# CW308T_AURIX.net
KiCad netlist of a schematic drawn in Altium Designer
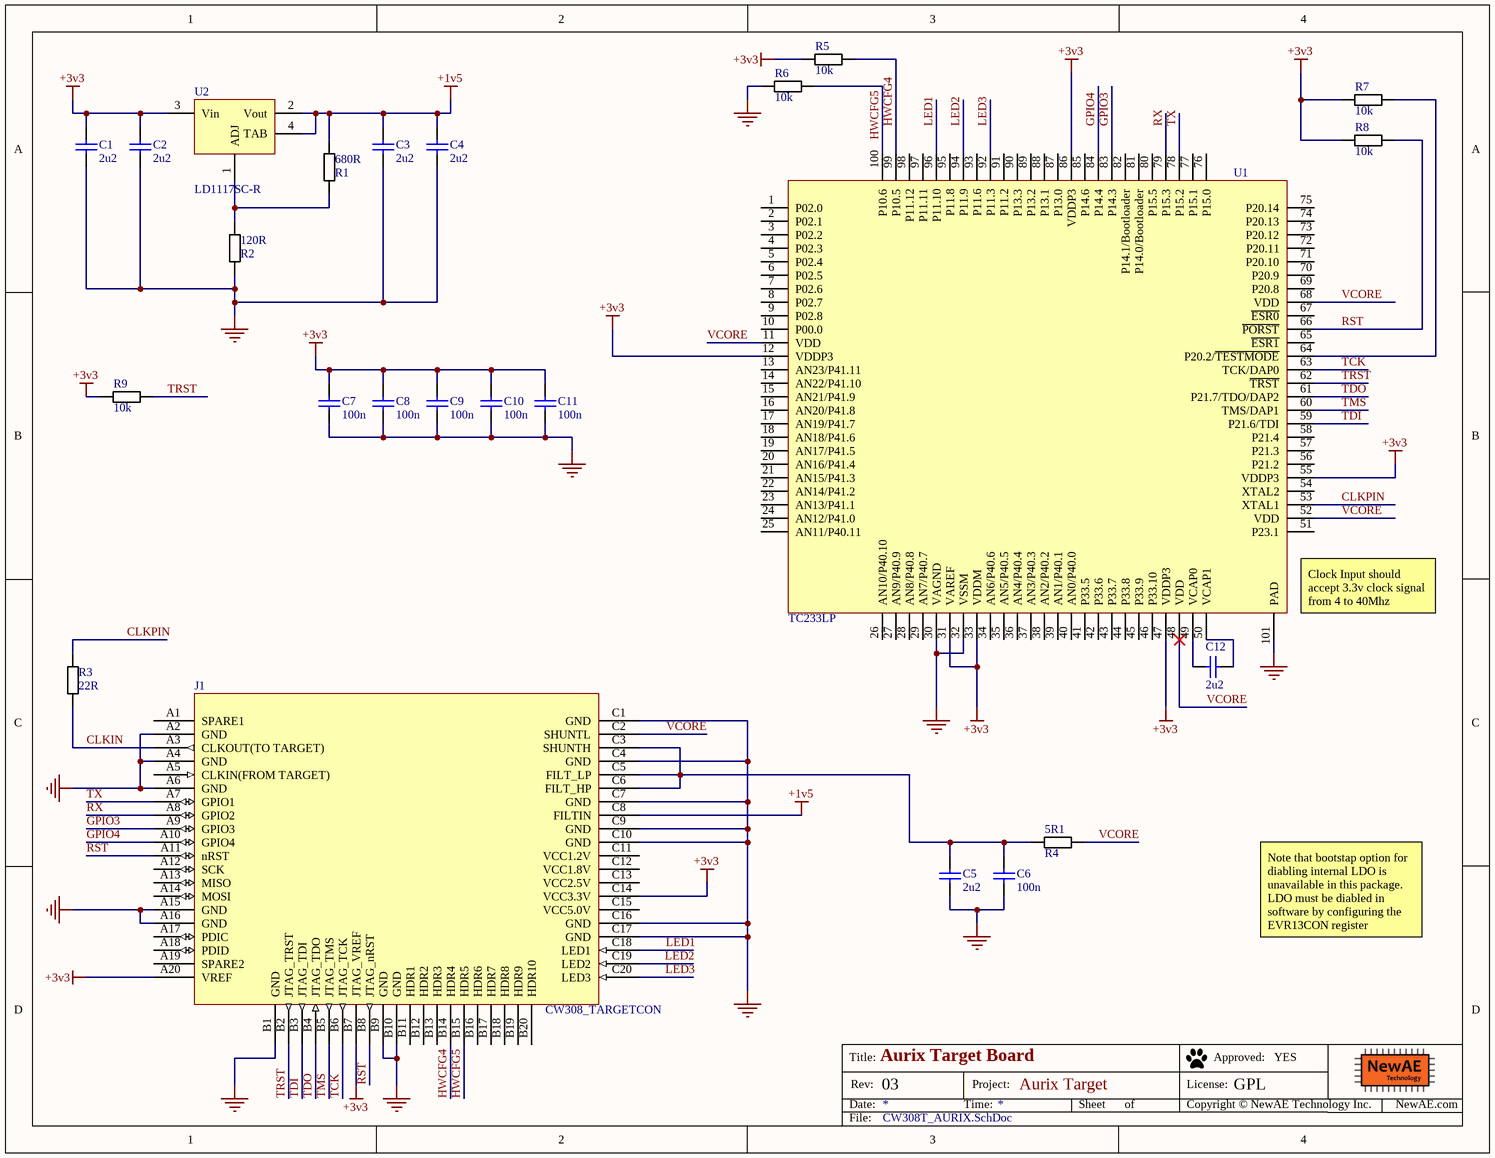
[diagram p0: CW308T_AURIX.SchDoc]

(export (version "E")
  (design (tool "Eeschema 10.0.6"))
  (components
    (comp (ref "C1")
      (value "2u2")
      (footprint "CAPC0603_M")
      (description "2u2, 0603")
      (fields (field (name "PART NUMBER") "CCHIP-2u2-0603"))
      (libsource (lib "NewAE_AltiumLib") (part "CAP"))
    )
    (comp (ref "C2")
      (value "2u2")
      (footprint "CAPC0603_M")
      (description "2u2, 0603")
      (fields (field (name "PART NUMBER") "CCHIP-2u2-0603"))
      (libsource (lib "NewAE_AltiumLib") (part "CAP"))
    )
    (comp (ref "C3")
      (value "2u2")
      (footprint "CAPC0603_M")
      (description "2u2, 0603")
      (fields (field (name "PART NUMBER") "CCHIP-2u2-0603"))
      (libsource (lib "NewAE_AltiumLib") (part "CAP"))
    )
    (comp (ref "C4")
      (value "2u2")
      (footprint "CAPC0603_M")
      (description "2u2, 0603")
      (fields (field (name "PART NUMBER") "CCHIP-2u2-0603"))
      (libsource (lib "NewAE_AltiumLib") (part "CAP"))
    )
    (comp (ref "C5")
      (value "2u2")
      (footprint "CAPC0603_M")
      (description "2u2, 0603")
      (fields (field (name "PART NUMBER") "CCHIP-2u2-0603"))
      (libsource (lib "NewAE_AltiumLib") (part "CAP"))
    )
    (comp (ref "C6")
      (value "100n")
      (footprint "CAPC0603_M")
      (description "100n, 0603")
      (fields (field (name "PART NUMBER") "CCHIP-100n-0603"))
      (libsource (lib "NewAE_AltiumLib") (part "CAP"))
    )
    (comp (ref "C7")
      (value "100n")
      (footprint "CAPC0603_M")
      (description "100n, 0603")
      (fields (field (name "PART NUMBER") "CCHIP-100n-0603"))
      (libsource (lib "NewAE_AltiumLib") (part "CAP"))
    )
    (comp (ref "C8")
      (value "100n")
      (footprint "CAPC0603_M")
      (description "100n, 0603")
      (fields (field (name "PART NUMBER") "CCHIP-100n-0603"))
      (libsource (lib "NewAE_AltiumLib") (part "CAP"))
    )
    (comp (ref "C9")
      (value "100n")
      (footprint "CAPC0603_M")
      (description "100n, 0603")
      (fields (field (name "PART NUMBER") "CCHIP-100n-0603"))
      (libsource (lib "NewAE_AltiumLib") (part "CAP"))
    )
    (comp (ref "C10")
      (value "100n")
      (footprint "CAPC0603_M")
      (description "100n, 0603")
      (fields (field (name "PART NUMBER") "CCHIP-100n-0603"))
      (libsource (lib "NewAE_AltiumLib") (part "CAP"))
    )
    (comp (ref "C11")
      (value "100n")
      (footprint "CAPC0603_M")
      (description "100n, 0603")
      (fields (field (name "PART NUMBER") "CCHIP-100n-0603"))
      (libsource (lib "NewAE_AltiumLib") (part "CAP"))
    )
    (comp (ref "C12")
      (value "2u2")
      (footprint "CAPC0603_M")
      (description "2u2, 0603")
      (fields (field (name "PART NUMBER") "CCHIP-2u2-0603"))
      (libsource (lib "NewAE_AltiumLib") (part "CAP"))
    )
    (comp (ref "J1")
      (value "CW308_TARGETCON")
      (footprint "CW308_TBOARD_CONN")
      (description "CW308 \"Standard\" Target Board Connector")
      (fields (field (name "PART NUMBER") "CW308_TBOARD"))
      (libsource (lib "NewAE_AltiumLib") (part "CW308_TBOARD"))
    )
    (comp (ref "R1")
      (value "680R")
      (footprint "RESC1608X55N")
      (description "680R res, 0603, 1%, 1/10W")
      (fields (field (name "PART NUMBER") "RCHIP-680R-0603") (field (name "TOLERANCE") "1%"))
      (libsource (lib "") (part "RES-EU_1"))
    )
    (comp (ref "R2")
      (value "120R")
      (footprint "RESC1608X55N")
      (description "120R res, 0603, 1%, 1/10W")
      (fields (field (name "PART NUMBER") "RCHIP-120R-0603") (field (name "TOLERANCE") "1%"))
      (libsource (lib "") (part "RES-EU_1"))
    )
    (comp (ref "R3")
      (value "22R")
      (footprint "RESC1608X55N")
      (description "22R res, 0603, 1%, 1/10W")
      (fields (field (name "PART NUMBER") "RCHIP-22R-0603") (field (name "TOLERANCE") "1%"))
      (libsource (lib "") (part "RES-EU_1"))
    )
    (comp (ref "R4")
      (value "5R1")
      (footprint "RESC1608X55N")
      (description "5R1 res, 0603, 1%, 1/10W")
      (fields (field (name "PART NUMBER") "RCHIP-5R1-0603") (field (name "TOLERANCE") "1%"))
      (libsource (lib "NewAE_AltiumLib") (part "RES-EU"))
    )
    (comp (ref "R5")
      (value "10k")
      (footprint "RESC1608X55N")
      (description "10k res, 0603, 1%, 1/10W")
      (fields (field (name "PART NUMBER") "RCHIP-10K-0603") (field (name "TOLERANCE") "1%"))
      (libsource (lib "NewAE_AltiumLib") (part "RES-EU"))
    )
    (comp (ref "R6")
      (value "10k")
      (footprint "RESC1608X55N")
      (description "10k res, 0603, 1%, 1/10W")
      (fields (field (name "PART NUMBER") "RCHIP-10K-0603") (field (name "TOLERANCE") "1%"))
      (libsource (lib "NewAE_AltiumLib") (part "RES-EU"))
    )
    (comp (ref "R7")
      (value "10k")
      (footprint "RESC1608X55N")
      (description "10k res, 0603, 1%, 1/10W")
      (fields (field (name "PART NUMBER") "RCHIP-10K-0603") (field (name "TOLERANCE") "1%"))
      (libsource (lib "") (part "RES-EU_2"))
    )
    (comp (ref "R8")
      (value "10k")
      (footprint "RESC1608X55N")
      (description "10k res, 0603, 1%, 1/10W")
      (fields (field (name "PART NUMBER") "RCHIP-10K-0603") (field (name "TOLERANCE") "1%"))
      (libsource (lib "NewAE_AltiumLib") (part "RES-EU"))
    )
    (comp (ref "R9")
      (value "10k")
      (footprint "RESC1608X55N")
      (description "10k res, 0603, 1%, 1/10W")
      (fields (field (name "PART NUMBER") "RCHIP-10K-0603") (field (name "TOLERANCE") "1%"))
      (libsource (lib "NewAE_AltiumLib") (part "RES-EU"))
    )
    (comp (ref "U1")
      (value "TC233LP")
      (footprint "PG-TQFP-100-23")
      (description "IC MCU 32BIT 2MB FLASH 100TQFP")
      (libsource (lib "NewAE_AltiumLib") (part "TC233LP"))
    )
    (comp (ref "U2") (value "LD1117SC-R") (libsource (lib "NewAE_AltiumLib") (part "LD1117SC-R")))
  )
  (nets
    (net (code "1") (name "+1v5") (class "Default")
      (node (ref "C3") (pin "1") (pinfunction "1_1") (pintype "passive"))
      (node (ref "C4") (pin "1") (pinfunction "1_1") (pintype "passive"))
      (node (ref "J1") (pin "C8") (pinfunction "FILTIN_C8") (pintype "passive"))
      (node (ref "R1") (pin "1") (pinfunction "1_1") (pintype "passive"))
      (node (ref "U2") (pin "2") (pinfunction "Vout_2") (pintype "passive"))
      (node (ref "U2") (pin "4") (pinfunction "TAB_4") (pintype "passive"))
    )
    (net (code "2") (name "+3v3") (class "Default")
      (node (ref "C1") (pin "1") (pinfunction "1_1") (pintype "passive"))
      (node (ref "C10") (pin "1") (pinfunction "1_1") (pintype "passive"))
      (node (ref "C11") (pin "1") (pinfunction "1_1") (pintype "passive"))
      (node (ref "C2") (pin "1") (pinfunction "1_1") (pintype "passive"))
      (node (ref "C7") (pin "1") (pinfunction "1_1") (pintype "passive"))
      (node (ref "C8") (pin "1") (pinfunction "1_1") (pintype "passive"))
      (node (ref "C9") (pin "1") (pinfunction "1_1") (pintype "passive"))
      (node (ref "J1") (pin "A20") (pinfunction "VREF_A20") (pintype "tri_state"))
      (node (ref "J1") (pin "B7") (pinfunction "JTAG_VREF_B7") (pintype "tri_state"))
      (node (ref "J1") (pin "C14") (pinfunction "VCC3.3V_C14") (pintype "power_in"))
      (node (ref "R5") (pin "1") (pinfunction "1_1") (pintype "passive"))
      (node (ref "R7") (pin "2") (pinfunction "2_2") (pintype "passive"))
      (node (ref "R8") (pin "1") (pinfunction "1_1") (pintype "passive"))
      (node (ref "R9") (pin "1") (pinfunction "1_1") (pintype "passive"))
      (node (ref "U1") (pin "12") (pinfunction "VDDP3_12") (pintype "passive"))
      (node (ref "U1") (pin "31") (pinfunction "VAREF_31") (pintype "passive"))
      (node (ref "U1") (pin "33") (pinfunction "VDDM_33") (pintype "passive"))
      (node (ref "U1") (pin "47") (pinfunction "VDDP3_47") (pintype "passive"))
      (node (ref "U1") (pin "55") (pinfunction "VDDP3_55") (pintype "passive"))
      (node (ref "U1") (pin "86") (pinfunction "VDDP3_86") (pintype "passive"))
      (node (ref "U2") (pin "3") (pinfunction "Vin_3") (pintype "passive"))
    )
    (net (code "3") (name "/CLKIN") (class "Default")
      (node (ref "J1") (pin "A3") (pinfunction "CLKOUT(TO_TARGET)_A3") (pintype "output"))
      (node (ref "R3") (pin "2") (pinfunction "2_2") (pintype "passive"))
    )
    (net (code "4") (name "/CLKPIN") (class "Default")
      (node (ref "R3") (pin "1") (pinfunction "1_1") (pintype "passive"))
      (node (ref "U1") (pin "53") (pinfunction "XTAL1_53") (pintype "passive"))
    )
    (net (code "5") (name "/GPIO3") (class "Default")
      (node (ref "J1") (pin "A9") (pinfunction "GPIO3_A9") (pintype "bidirectional"))
      (node (ref "U1") (pin "83") (pinfunction "P14.3_83") (pintype "passive"))
    )
    (net (code "6") (name "/GPIO4") (class "Default")
      (node (ref "J1") (pin "A10") (pinfunction "GPIO4_A10") (pintype "bidirectional"))
      (node (ref "U1") (pin "84") (pinfunction "P14.4_84") (pintype "passive"))
    )
    (net (code "7") (name "/HWCFG4") (class "Default")
      (node (ref "J1") (pin "B14") (pinfunction "HDR4_B14") (pintype "passive"))
      (node (ref "R5") (pin "2") (pinfunction "2_2") (pintype "passive"))
      (node (ref "U1") (pin "99") (pinfunction "P10.5_99") (pintype "passive"))
    )
    (net (code "8") (name "/HWCFG5") (class "Default")
      (node (ref "J1") (pin "B15") (pinfunction "HDR5_B15") (pintype "passive"))
      (node (ref "R6") (pin "2") (pinfunction "2_2") (pintype "passive"))
      (node (ref "U1") (pin "100") (pinfunction "P10.6_100") (pintype "passive"))
    )
    (net (code "9") (name "/LED1") (class "Default")
      (node (ref "J1") (pin "C18") (pinfunction "LED1_C18") (pintype "input"))
      (node (ref "U1") (pin "96") (pinfunction "P11.10_96") (pintype "passive"))
    )
    (net (code "10") (name "/LED2") (class "Default")
      (node (ref "J1") (pin "C19") (pinfunction "LED2_C19") (pintype "input"))
      (node (ref "U1") (pin "94") (pinfunction "P11.9_94") (pintype "passive"))
    )
    (net (code "11") (name "/LED3") (class "Default")
      (node (ref "J1") (pin "C20") (pinfunction "LED3_C20") (pintype "input"))
      (node (ref "U1") (pin "92") (pinfunction "P11.3_92") (pintype "passive"))
    )
    (net (code "12") (name "/RST") (class "Default")
      (node (ref "J1") (pin "A11") (pinfunction "nRST_A11") (pintype "bidirectional"))
      (node (ref "J1") (pin "B8") (pinfunction "JTAG_nRST_B8") (pintype "output"))
      (node (ref "R8") (pin "2") (pinfunction "2_2") (pintype "passive"))
      (node (ref "U1") (pin "66") (pinfunction "~{PORST}_66") (pintype "passive"))
    )
    (net (code "13") (name "/RX") (class "Default")
      (node (ref "J1") (pin "A8") (pinfunction "GPIO2_A8") (pintype "bidirectional"))
      (node (ref "U1") (pin "79") (pinfunction "P15.3_79") (pintype "passive"))
    )
    (net (code "14") (name "/TCK") (class "Default")
      (node (ref "J1") (pin "B6") (pinfunction "JTAG_TCK_B6") (pintype "output"))
      (node (ref "U1") (pin "63") (pinfunction "TCK/DAP0_63") (pintype "passive"))
    )
    (net (code "15") (name "/TDI") (class "Default")
      (node (ref "J1") (pin "B3") (pinfunction "JTAG_TDI_B3") (pintype "output"))
      (node (ref "U1") (pin "59") (pinfunction "P21.6/TDI_59") (pintype "passive"))
    )
    (net (code "16") (name "/TDO") (class "Default")
      (node (ref "J1") (pin "B4") (pinfunction "JTAG_TDO_B4") (pintype "input"))
      (node (ref "U1") (pin "61") (pinfunction "P21.7/TDO/DAP2_61") (pintype "passive"))
    )
    (net (code "17") (name "/TMS") (class "Default")
      (node (ref "J1") (pin "B5") (pinfunction "JTAG_TMS_B5") (pintype "output"))
      (node (ref "U1") (pin "60") (pinfunction "TMS/DAP1_60") (pintype "passive"))
    )
    (net (code "18") (name "/TRST") (class "Default")
      (node (ref "J1") (pin "B2") (pinfunction "JTAG_TRST_B2") (pintype "output"))
      (node (ref "R9") (pin "2") (pinfunction "2_2") (pintype "passive"))
      (node (ref "U1") (pin "62") (pinfunction "~{TRST}_62") (pintype "passive"))
    )
    (net (code "19") (name "/TX") (class "Default")
      (node (ref "J1") (pin "A7") (pinfunction "GPIO1_A7") (pintype "bidirectional"))
      (node (ref "U1") (pin "78") (pinfunction "P15.2_78") (pintype "passive"))
    )
    (net (code "20") (name "/VCORE") (class "Default")
      (node (ref "J1") (pin "C2") (pinfunction "SHUNTL_C2") (pintype "passive"))
      (node (ref "R4") (pin "2") (pinfunction "2_2") (pintype "passive"))
      (node (ref "U1") (pin "11") (pinfunction "VDD_11") (pintype "passive"))
      (node (ref "U1") (pin "48") (pinfunction "VDD_48") (pintype "passive"))
      (node (ref "U1") (pin "52") (pinfunction "VDD_52") (pintype "passive"))
      (node (ref "U1") (pin "68") (pinfunction "VDD_68") (pintype "passive"))
    )
    (net (code "21") (name "GND") (class "Default")
      (node (ref "C1") (pin "2") (pinfunction "2_2") (pintype "passive"))
      (node (ref "C10") (pin "2") (pinfunction "2_2") (pintype "passive"))
      (node (ref "C11") (pin "2") (pinfunction "2_2") (pintype "passive"))
      (node (ref "C2") (pin "2") (pinfunction "2_2") (pintype "passive"))
      (node (ref "C3") (pin "2") (pinfunction "2_2") (pintype "passive"))
      (node (ref "C4") (pin "2") (pinfunction "2_2") (pintype "passive"))
      (node (ref "C5") (pin "2") (pinfunction "2_2") (pintype "passive"))
      (node (ref "C6") (pin "2") (pinfunction "2_2") (pintype "passive"))
      (node (ref "C7") (pin "2") (pinfunction "2_2") (pintype "passive"))
      (node (ref "C8") (pin "2") (pinfunction "2_2") (pintype "passive"))
      (node (ref "C9") (pin "2") (pinfunction "2_2") (pintype "passive"))
      (node (ref "J1") (pin "A15") (pinfunction "GND_A15") (pintype "passive"))
      (node (ref "J1") (pin "A16") (pinfunction "GND_A16") (pintype "passive"))
      (node (ref "J1") (pin "A2") (pinfunction "GND_A2") (pintype "passive"))
      (node (ref "J1") (pin "A4") (pinfunction "GND_A4") (pintype "passive"))
      (node (ref "J1") (pin "A6") (pinfunction "GND_A6") (pintype "power_in"))
      (node (ref "J1") (pin "B1") (pinfunction "GND_B1") (pintype "passive"))
      (node (ref "J1") (pin "B10") (pinfunction "GND_B10") (pintype "passive"))
      (node (ref "J1") (pin "B9") (pinfunction "GND_B9") (pintype "passive"))
      (node (ref "J1") (pin "C1") (pinfunction "GND_C1") (pintype "power_in"))
      (node (ref "J1") (pin "C10") (pinfunction "GND_C10") (pintype "power_in"))
      (node (ref "J1") (pin "C16") (pinfunction "GND_C16") (pintype "power_in"))
      (node (ref "J1") (pin "C17") (pinfunction "GND_C17") (pintype "power_in"))
      (node (ref "J1") (pin "C4") (pinfunction "GND_C4") (pintype "power_in"))
      (node (ref "J1") (pin "C7") (pinfunction "GND_C7") (pintype "power_in"))
      (node (ref "J1") (pin "C9") (pinfunction "GND_C9") (pintype "power_in"))
      (node (ref "R2") (pin "2") (pinfunction "2_2") (pintype "passive"))
      (node (ref "R6") (pin "1") (pinfunction "1_1") (pintype "passive"))
      (node (ref "U1") (pin "101") (pinfunction "PAD_101") (pintype "passive"))
      (node (ref "U1") (pin "30") (pinfunction "VAGND_30") (pintype "passive"))
      (node (ref "U1") (pin "32") (pinfunction "VSSM_32") (pintype "passive"))
    )
    (net (code "22") (name "Net-(J1-FILT_HP)") (class "Default")
      (node (ref "C5") (pin "1") (pinfunction "1_1") (pintype "passive"))
      (node (ref "C6") (pin "1") (pinfunction "1_1") (pintype "passive"))
      (node (ref "J1") (pin "C3") (pinfunction "SHUNTH_C3") (pintype "passive"))
      (node (ref "J1") (pin "C5") (pinfunction "FILT_LP_C5") (pintype "passive"))
      (node (ref "J1") (pin "C6") (pinfunction "FILT_HP_C6") (pintype "passive"))
      (node (ref "R4") (pin "1") (pinfunction "1_1") (pintype "passive"))
    )
    (net (code "23") (name "Net-(U1-P20.2{slash}~{TESTMODE})") (class "Default")
      (node (ref "R7") (pin "1") (pinfunction "1_1") (pintype "passive"))
      (node (ref "U1") (pin "64") (pinfunction "P20.2/~{TESTMODE}_64") (pintype "passive"))
    )
    (net (code "24") (name "Net-(U1-VCAP0)") (class "Default")
      (node (ref "C12") (pin "1") (pinfunction "1_1") (pintype "passive"))
      (node (ref "U1") (pin "49") (pinfunction "VCAP0_49") (pintype "passive"))
    )
    (net (code "25") (name "Net-(U1-VCAP1)") (class "Default")
      (node (ref "C12") (pin "2") (pinfunction "2_2") (pintype "passive"))
      (node (ref "U1") (pin "50") (pinfunction "VCAP1_50") (pintype "passive"))
    )
    (net (code "26") (name "Net-(U2-ADJ)") (class "Default")
      (node (ref "R1") (pin "2") (pinfunction "2_2") (pintype "passive"))
      (node (ref "R2") (pin "1") (pinfunction "1_1") (pintype "passive"))
      (node (ref "U2") (pin "1") (pinfunction "ADJ_1") (pintype "passive"))
    )
    (net (code "27") (name "unconnected-(J1-CLKIN(FROM_TARGET)-PadA5)") (class "Default")
      (node (ref "J1") (pin "A5") (pinfunction "CLKIN(FROM_TARGET)_A5") (pintype "input"))
    )
    (net (code "28") (name "unconnected-(J1-HDR1-PadB11)") (class "Default")
      (node (ref "J1") (pin "B11") (pinfunction "HDR1_B11") (pintype "passive"))
    )
    (net (code "29") (name "unconnected-(J1-HDR2-PadB12)") (class "Default")
      (node (ref "J1") (pin "B12") (pinfunction "HDR2_B12") (pintype "passive"))
    )
    (net (code "30") (name "unconnected-(J1-HDR3-PadB13)") (class "Default")
      (node (ref "J1") (pin "B13") (pinfunction "HDR3_B13") (pintype "passive"))
    )
    (net (code "31") (name "unconnected-(J1-HDR6-PadB16)") (class "Default")
      (node (ref "J1") (pin "B16") (pinfunction "HDR6_B16") (pintype "passive"))
    )
    (net (code "32") (name "unconnected-(J1-HDR7-PadB17)") (class "Default")
      (node (ref "J1") (pin "B17") (pinfunction "HDR7_B17") (pintype "passive"))
    )
    (net (code "33") (name "unconnected-(J1-HDR8-PadB18)") (class "Default")
      (node (ref "J1") (pin "B18") (pinfunction "HDR8_B18") (pintype "passive"))
    )
    (net (code "34") (name "unconnected-(J1-HDR9-PadB19)") (class "Default")
      (node (ref "J1") (pin "B19") (pinfunction "HDR9_B19") (pintype "passive"))
    )
    (net (code "35") (name "unconnected-(J1-HDR10-PadB20)") (class "Default")
      (node (ref "J1") (pin "B20") (pinfunction "HDR10_B20") (pintype "passive"))
    )
    (net (code "36") (name "unconnected-(J1-MISO-PadA13)") (class "Default")
      (node (ref "J1") (pin "A13") (pinfunction "MISO_A13") (pintype "bidirectional"))
    )
    (net (code "37") (name "unconnected-(J1-MOSI-PadA14)") (class "Default")
      (node (ref "J1") (pin "A14") (pinfunction "MOSI_A14") (pintype "bidirectional"))
    )
    (net (code "38") (name "unconnected-(J1-PDIC-PadA17)") (class "Default")
      (node (ref "J1") (pin "A17") (pinfunction "PDIC_A17") (pintype "bidirectional"))
    )
    (net (code "39") (name "unconnected-(J1-PDID-PadA18)") (class "Default")
      (node (ref "J1") (pin "A18") (pinfunction "PDID_A18") (pintype "bidirectional"))
    )
    (net (code "40") (name "unconnected-(J1-SCK-PadA12)") (class "Default")
      (node (ref "J1") (pin "A12") (pinfunction "SCK_A12") (pintype "bidirectional"))
    )
    (net (code "41") (name "unconnected-(J1-SPARE1-PadA1)") (class "Default")
      (node (ref "J1") (pin "A1") (pinfunction "SPARE1_A1") (pintype "passive"))
    )
    (net (code "42") (name "unconnected-(J1-SPARE2-PadA19)") (class "Default")
      (node (ref "J1") (pin "A19") (pinfunction "SPARE2_A19") (pintype "passive"))
    )
    (net (code "43") (name "unconnected-(J1-VCC1.2V-PadC11)") (class "Default")
      (node (ref "J1") (pin "C11") (pinfunction "VCC1.2V_C11") (pintype "power_in"))
    )
    (net (code "44") (name "unconnected-(J1-VCC1.8V-PadC12)") (class "Default")
      (node (ref "J1") (pin "C12") (pinfunction "VCC1.8V_C12") (pintype "power_in"))
    )
    (net (code "45") (name "unconnected-(J1-VCC2.5V-PadC13)") (class "Default")
      (node (ref "J1") (pin "C13") (pinfunction "VCC2.5V_C13") (pintype "power_in"))
    )
    (net (code "46") (name "unconnected-(J1-VCC5.0V-PadC15)") (class "Default")
      (node (ref "J1") (pin "C15") (pinfunction "VCC5.0V_C15") (pintype "power_in"))
    )
    (net (code "47") (name "unconnected-(U1-AN0{slash}P40.0-Pad40)") (class "Default")
      (node (ref "U1") (pin "40") (pinfunction "AN0/P40.0_40") (pintype "passive"))
    )
    (net (code "48") (name "unconnected-(U1-AN1{slash}P40.1-Pad39)") (class "Default")
      (node (ref "U1") (pin "39") (pinfunction "AN1/P40.1_39") (pintype "passive"))
    )
    (net (code "49") (name "unconnected-(U1-AN2{slash}P40.2-Pad38)") (class "Default")
      (node (ref "U1") (pin "38") (pinfunction "AN2/P40.2_38") (pintype "passive"))
    )
    (net (code "50") (name "unconnected-(U1-AN3{slash}P40.3-Pad37)") (class "Default")
      (node (ref "U1") (pin "37") (pinfunction "AN3/P40.3_37") (pintype "passive"))
    )
    (net (code "51") (name "unconnected-(U1-AN4{slash}P40.4-Pad36)") (class "Default")
      (node (ref "U1") (pin "36") (pinfunction "AN4/P40.4_36") (pintype "passive"))
    )
    (net (code "52") (name "unconnected-(U1-AN5{slash}P40.5-Pad35)") (class "Default")
      (node (ref "U1") (pin "35") (pinfunction "AN5/P40.5_35") (pintype "passive"))
    )
    (net (code "53") (name "unconnected-(U1-AN6{slash}P40.6-Pad34)") (class "Default")
      (node (ref "U1") (pin "34") (pinfunction "AN6/P40.6_34") (pintype "passive"))
    )
    (net (code "54") (name "unconnected-(U1-AN7{slash}P40.7-Pad29)") (class "Default")
      (node (ref "U1") (pin "29") (pinfunction "AN7/P40.7_29") (pintype "passive"))
    )
    (net (code "55") (name "unconnected-(U1-AN8{slash}P40.8-Pad28)") (class "Default")
      (node (ref "U1") (pin "28") (pinfunction "AN8/P40.8_28") (pintype "passive"))
    )
    (net (code "56") (name "unconnected-(U1-AN9{slash}P40.9-Pad27)") (class "Default")
      (node (ref "U1") (pin "27") (pinfunction "AN9/P40.9_27") (pintype "passive"))
    )
    (net (code "57") (name "unconnected-(U1-AN10{slash}P40.10-Pad26)") (class "Default")
      (node (ref "U1") (pin "26") (pinfunction "AN10/P40.10_26") (pintype "passive"))
    )
    (net (code "58") (name "unconnected-(U1-AN11{slash}P40.11-Pad25)") (class "Default")
      (node (ref "U1") (pin "25") (pinfunction "AN11/P40.11_25") (pintype "passive"))
    )
    (net (code "59") (name "unconnected-(U1-AN12{slash}P41.0-Pad24)") (class "Default")
      (node (ref "U1") (pin "24") (pinfunction "AN12/P41.0_24") (pintype "passive"))
    )
    (net (code "60") (name "unconnected-(U1-AN13{slash}P41.1-Pad23)") (class "Default")
      (node (ref "U1") (pin "23") (pinfunction "AN13/P41.1_23") (pintype "passive"))
    )
    (net (code "61") (name "unconnected-(U1-AN14{slash}P41.2-Pad22)") (class "Default")
      (node (ref "U1") (pin "22") (pinfunction "AN14/P41.2_22") (pintype "passive"))
    )
    (net (code "62") (name "unconnected-(U1-AN15{slash}P41.3-Pad21)") (class "Default")
      (node (ref "U1") (pin "21") (pinfunction "AN15/P41.3_21") (pintype "passive"))
    )
    (net (code "63") (name "unconnected-(U1-AN16{slash}P41.4-Pad20)") (class "Default")
      (node (ref "U1") (pin "20") (pinfunction "AN16/P41.4_20") (pintype "passive"))
    )
    (net (code "64") (name "unconnected-(U1-AN17{slash}P41.5-Pad19)") (class "Default")
      (node (ref "U1") (pin "19") (pinfunction "AN17/P41.5_19") (pintype "passive"))
    )
    (net (code "65") (name "unconnected-(U1-AN18{slash}P41.6-Pad18)") (class "Default")
      (node (ref "U1") (pin "18") (pinfunction "AN18/P41.6_18") (pintype "passive"))
    )
    (net (code "66") (name "unconnected-(U1-AN19{slash}P41.7-Pad17)") (class "Default")
      (node (ref "U1") (pin "17") (pinfunction "AN19/P41.7_17") (pintype "passive"))
    )
    (net (code "67") (name "unconnected-(U1-AN20{slash}P41.8-Pad16)") (class "Default")
      (node (ref "U1") (pin "16") (pinfunction "AN20/P41.8_16") (pintype "passive"))
    )
    (net (code "68") (name "unconnected-(U1-AN21{slash}P41.9-Pad15)") (class "Default")
      (node (ref "U1") (pin "15") (pinfunction "AN21/P41.9_15") (pintype "passive"))
    )
    (net (code "69") (name "unconnected-(U1-AN22{slash}P41.10-Pad14)") (class "Default")
      (node (ref "U1") (pin "14") (pinfunction "AN22/P41.10_14") (pintype "passive"))
    )
    (net (code "70") (name "unconnected-(U1-AN23{slash}P41.11-Pad13)") (class "Default")
      (node (ref "U1") (pin "13") (pinfunction "AN23/P41.11_13") (pintype "passive"))
    )
    (net (code "71") (name "unconnected-(U1-P00.0-Pad10)") (class "Default")
      (node (ref "U1") (pin "10") (pinfunction "P00.0_10") (pintype "passive"))
    )
    (net (code "72") (name "unconnected-(U1-P02.0-Pad1)") (class "Default")
      (node (ref "U1") (pin "1") (pinfunction "P02.0_1") (pintype "passive"))
    )
    (net (code "73") (name "unconnected-(U1-P02.1-Pad2)") (class "Default")
      (node (ref "U1") (pin "2") (pinfunction "P02.1_2") (pintype "passive"))
    )
    (net (code "74") (name "unconnected-(U1-P02.2-Pad3)") (class "Default")
      (node (ref "U1") (pin "3") (pinfunction "P02.2_3") (pintype "passive"))
    )
    (net (code "75") (name "unconnected-(U1-P02.3-Pad4)") (class "Default")
      (node (ref "U1") (pin "4") (pinfunction "P02.3_4") (pintype "passive"))
    )
    (net (code "76") (name "unconnected-(U1-P02.4-Pad5)") (class "Default")
      (node (ref "U1") (pin "5") (pinfunction "P02.4_5") (pintype "passive"))
    )
    (net (code "77") (name "unconnected-(U1-P02.5-Pad6)") (class "Default")
      (node (ref "U1") (pin "6") (pinfunction "P02.5_6") (pintype "passive"))
    )
    (net (code "78") (name "unconnected-(U1-P02.6-Pad7)") (class "Default")
      (node (ref "U1") (pin "7") (pinfunction "P02.6_7") (pintype "passive"))
    )
    (net (code "79") (name "unconnected-(U1-P02.7-Pad8)") (class "Default")
      (node (ref "U1") (pin "8") (pinfunction "P02.7_8") (pintype "passive"))
    )
    (net (code "80") (name "unconnected-(U1-P02.8-Pad9)") (class "Default")
      (node (ref "U1") (pin "9") (pinfunction "P02.8_9") (pintype "passive"))
    )
    (net (code "81") (name "unconnected-(U1-P11.2-Pad91)") (class "Default")
      (node (ref "U1") (pin "91") (pinfunction "P11.2_91") (pintype "passive"))
    )
    (net (code "82") (name "unconnected-(U1-P11.6-Pad93)") (class "Default")
      (node (ref "U1") (pin "93") (pinfunction "P11.6_93") (pintype "passive"))
    )
    (net (code "83") (name "unconnected-(U1-P11.8-Pad95)") (class "Default")
      (node (ref "U1") (pin "95") (pinfunction "P11.8_95") (pintype "passive"))
    )
    (net (code "84") (name "unconnected-(U1-P11.11-Pad97)") (class "Default")
      (node (ref "U1") (pin "97") (pinfunction "P11.11_97") (pintype "passive"))
    )
    (net (code "85") (name "unconnected-(U1-P11.12-Pad98)") (class "Default")
      (node (ref "U1") (pin "98") (pinfunction "P11.12_98") (pintype "passive"))
    )
    (net (code "86") (name "unconnected-(U1-P13.0-Pad87)") (class "Default")
      (node (ref "U1") (pin "87") (pinfunction "P13.0_87") (pintype "passive"))
    )
    (net (code "87") (name "unconnected-(U1-P13.1-Pad88)") (class "Default")
      (node (ref "U1") (pin "88") (pinfunction "P13.1_88") (pintype "passive"))
    )
    (net (code "88") (name "unconnected-(U1-P13.2-Pad89)") (class "Default")
      (node (ref "U1") (pin "89") (pinfunction "P13.2_89") (pintype "passive"))
    )
    (net (code "89") (name "unconnected-(U1-P13.3-Pad90)") (class "Default")
      (node (ref "U1") (pin "90") (pinfunction "P13.3_90") (pintype "passive"))
    )
    (net (code "90") (name "unconnected-(U1-P14.0{slash}Bootloader-Pad81)") (class "Default")
      (node (ref "U1") (pin "81") (pinfunction "P14.0/Bootloader_81") (pintype "passive"))
    )
    (net (code "91") (name "unconnected-(U1-P14.1{slash}Bootloader-Pad82)") (class "Default")
      (node (ref "U1") (pin "82") (pinfunction "P14.1/Bootloader_82") (pintype "passive"))
    )
    (net (code "92") (name "unconnected-(U1-P14.6-Pad85)") (class "Default")
      (node (ref "U1") (pin "85") (pinfunction "P14.6_85") (pintype "passive"))
    )
    (net (code "93") (name "unconnected-(U1-P15.0-Pad76)") (class "Default")
      (node (ref "U1") (pin "76") (pinfunction "P15.0_76") (pintype "passive"))
    )
    (net (code "94") (name "unconnected-(U1-P15.1-Pad77)") (class "Default")
      (node (ref "U1") (pin "77") (pinfunction "P15.1_77") (pintype "passive"))
    )
    (net (code "95") (name "unconnected-(U1-P15.5-Pad80)") (class "Default")
      (node (ref "U1") (pin "80") (pinfunction "P15.5_80") (pintype "passive"))
    )
    (net (code "96") (name "unconnected-(U1-P20.8-Pad69)") (class "Default")
      (node (ref "U1") (pin "69") (pinfunction "P20.8_69") (pintype "passive"))
    )
    (net (code "97") (name "unconnected-(U1-P20.9-Pad70)") (class "Default")
      (node (ref "U1") (pin "70") (pinfunction "P20.9_70") (pintype "passive"))
    )
    (net (code "98") (name "unconnected-(U1-P20.10-Pad71)") (class "Default")
      (node (ref "U1") (pin "71") (pinfunction "P20.10_71") (pintype "passive"))
    )
    (net (code "99") (name "unconnected-(U1-P20.11-Pad72)") (class "Default")
      (node (ref "U1") (pin "72") (pinfunction "P20.11_72") (pintype "passive"))
    )
    (net (code "100") (name "unconnected-(U1-P20.12-Pad73)") (class "Default")
      (node (ref "U1") (pin "73") (pinfunction "P20.12_73") (pintype "passive"))
    )
    (net (code "101") (name "unconnected-(U1-P20.13-Pad74)") (class "Default")
      (node (ref "U1") (pin "74") (pinfunction "P20.13_74") (pintype "passive"))
    )
    (net (code "102") (name "unconnected-(U1-P20.14-Pad75)") (class "Default")
      (node (ref "U1") (pin "75") (pinfunction "P20.14_75") (pintype "passive"))
    )
    (net (code "103") (name "unconnected-(U1-P21.2-Pad56)") (class "Default")
      (node (ref "U1") (pin "56") (pinfunction "P21.2_56") (pintype "passive"))
    )
    (net (code "104") (name "unconnected-(U1-P21.3-Pad57)") (class "Default")
      (node (ref "U1") (pin "57") (pinfunction "P21.3_57") (pintype "passive"))
    )
    (net (code "105") (name "unconnected-(U1-P21.4-Pad58)") (class "Default")
      (node (ref "U1") (pin "58") (pinfunction "P21.4_58") (pintype "passive"))
    )
    (net (code "106") (name "unconnected-(U1-P23.1-Pad51)") (class "Default")
      (node (ref "U1") (pin "51") (pinfunction "P23.1_51") (pintype "passive"))
    )
    (net (code "107") (name "unconnected-(U1-P33.5-Pad41)") (class "Default")
      (node (ref "U1") (pin "41") (pinfunction "P33.5_41") (pintype "passive"))
    )
    (net (code "108") (name "unconnected-(U1-P33.6-Pad42)") (class "Default")
      (node (ref "U1") (pin "42") (pinfunction "P33.6_42") (pintype "passive"))
    )
    (net (code "109") (name "unconnected-(U1-P33.7-Pad43)") (class "Default")
      (node (ref "U1") (pin "43") (pinfunction "P33.7_43") (pintype "passive"))
    )
    (net (code "110") (name "unconnected-(U1-P33.8-Pad44)") (class "Default")
      (node (ref "U1") (pin "44") (pinfunction "P33.8_44") (pintype "passive"))
    )
    (net (code "111") (name "unconnected-(U1-P33.9-Pad45)") (class "Default")
      (node (ref "U1") (pin "45") (pinfunction "P33.9_45") (pintype "passive"))
    )
    (net (code "112") (name "unconnected-(U1-P33.10-Pad46)") (class "Default")
      (node (ref "U1") (pin "46") (pinfunction "P33.10_46") (pintype "passive"))
    )
    (net (code "113") (name "unconnected-(U1-XTAL2-Pad54)") (class "Default")
      (node (ref "U1") (pin "54") (pinfunction "XTAL2_54") (pintype "passive"))
    )
    (net (code "114") (name "unconnected-(U1-~{ESR0}-Pad67)") (class "Default")
      (node (ref "U1") (pin "67") (pinfunction "~{ESR0}_67") (pintype "passive"))
    )
    (net (code "115") (name "unconnected-(U1-~{ESR1}-Pad65)") (class "Default")
      (node (ref "U1") (pin "65") (pinfunction "~{ESR1}_65") (pintype "passive"))
    )
  )
)
